# AmiiboPI.net
KiCad netlist of a schematic drawn in EAGLE
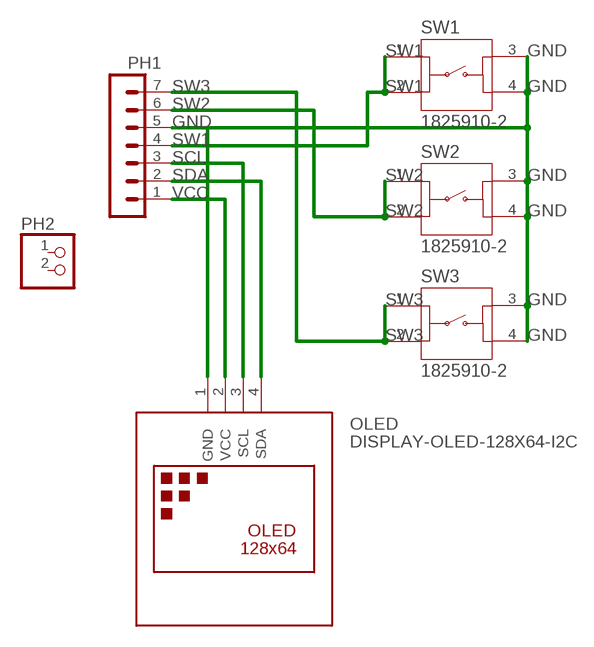
[diagram p0: schematic, sheet 1]

(export (version "E")
  (design (tool "Eeschema 10.0.6"))
  (components
    (comp (ref "OLED")
      (value "DISPLAY-OLED-128X64-I2C")
      (footprint "eagle-import:DISPLAY-OLED-128X64-I2C")
      (libsource (lib "eagle-import") (part "DISPLAY-OLED-128X64-I2C"))
    )
    (comp (ref "PH1")
      (value "MA07-1")
      (footprint "eagle-import:MA07-1")
      (libsource (lib "eagle-import") (part "MA07-1"))
    )
    (comp (ref "PH2")
      (value "PINHD-1X2")
      (footprint "eagle-import:1X02")
      (libsource (lib "eagle-import") (part "PINHD-1X2"))
    )
    (comp (ref "SW1")
      (value "1825910-2")
      (footprint "eagle-import:TE_1825910-2")
      (fields (field (name "MF") "TE Connectivity"))
      (libsource (lib "eagle-import") (part "1825910-2"))
    )
    (comp (ref "SW2")
      (value "1825910-2")
      (footprint "eagle-import:TE_1825910-2")
      (fields (field (name "MF") "TE Connectivity"))
      (libsource (lib "eagle-import") (part "1825910-2"))
    )
    (comp (ref "SW3")
      (value "1825910-2")
      (footprint "eagle-import:TE_1825910-2")
      (fields (field (name "MF") "TE Connectivity"))
      (libsource (lib "eagle-import") (part "1825910-2"))
    )
  )
  (nets
    (net (code "1") (name "/GND") (class "Default")
      (node (ref "OLED") (pin "1") (pinfunction "GND_1") (pintype "power_in"))
      (node (ref "PH1") (pin "5") (pinfunction "5_5") (pintype "passive"))
      (node (ref "SW1") (pin "3") (pinfunction "3_3") (pintype "passive"))
      (node (ref "SW1") (pin "4") (pinfunction "4_4") (pintype "passive"))
      (node (ref "SW2") (pin "3") (pinfunction "3_3") (pintype "passive"))
      (node (ref "SW2") (pin "4") (pinfunction "4_4") (pintype "passive"))
      (node (ref "SW3") (pin "3") (pinfunction "3_3") (pintype "passive"))
      (node (ref "SW3") (pin "4") (pinfunction "4_4") (pintype "passive"))
    )
    (net (code "2") (name "/SCL") (class "Default")
      (node (ref "OLED") (pin "3") (pinfunction "SCL_3") (pintype "bidirectional"))
      (node (ref "PH1") (pin "3") (pinfunction "3_3") (pintype "passive"))
    )
    (net (code "3") (name "/SDA") (class "Default")
      (node (ref "OLED") (pin "4") (pinfunction "SDA_4") (pintype "bidirectional"))
      (node (ref "PH1") (pin "2") (pinfunction "2_2") (pintype "passive"))
    )
    (net (code "4") (name "/SW1") (class "Default")
      (node (ref "PH1") (pin "4") (pinfunction "4_4") (pintype "passive"))
      (node (ref "SW1") (pin "1") (pinfunction "1_1") (pintype "passive"))
      (node (ref "SW1") (pin "2") (pinfunction "2_2") (pintype "passive"))
    )
    (net (code "5") (name "/SW2") (class "Default")
      (node (ref "PH1") (pin "6") (pinfunction "6_6") (pintype "passive"))
      (node (ref "SW2") (pin "1") (pinfunction "1_1") (pintype "passive"))
      (node (ref "SW2") (pin "2") (pinfunction "2_2") (pintype "passive"))
    )
    (net (code "6") (name "/SW3") (class "Default")
      (node (ref "PH1") (pin "7") (pinfunction "7_7") (pintype "passive"))
      (node (ref "SW3") (pin "1") (pinfunction "1_1") (pintype "passive"))
      (node (ref "SW3") (pin "2") (pinfunction "2_2") (pintype "passive"))
    )
    (net (code "7") (name "/VCC") (class "Default")
      (node (ref "OLED") (pin "2") (pinfunction "VCC_2") (pintype "power_in"))
      (node (ref "PH1") (pin "1") (pinfunction "1_1") (pintype "passive"))
    )
    (net (code "8") (name "unconnected-(PH2-Pad1)") (class "Default")
      (node (ref "PH2") (pin "1") (pinfunction "1_1") (pintype "passive"))
    )
    (net (code "9") (name "unconnected-(PH2-Pad2)") (class "Default")
      (node (ref "PH2") (pin "2") (pinfunction "2_2") (pintype "passive"))
    )
  )
)
